# 20190801_MemEx_v1_1.net
KiCad netlist of a schematic drawn in EAGLE
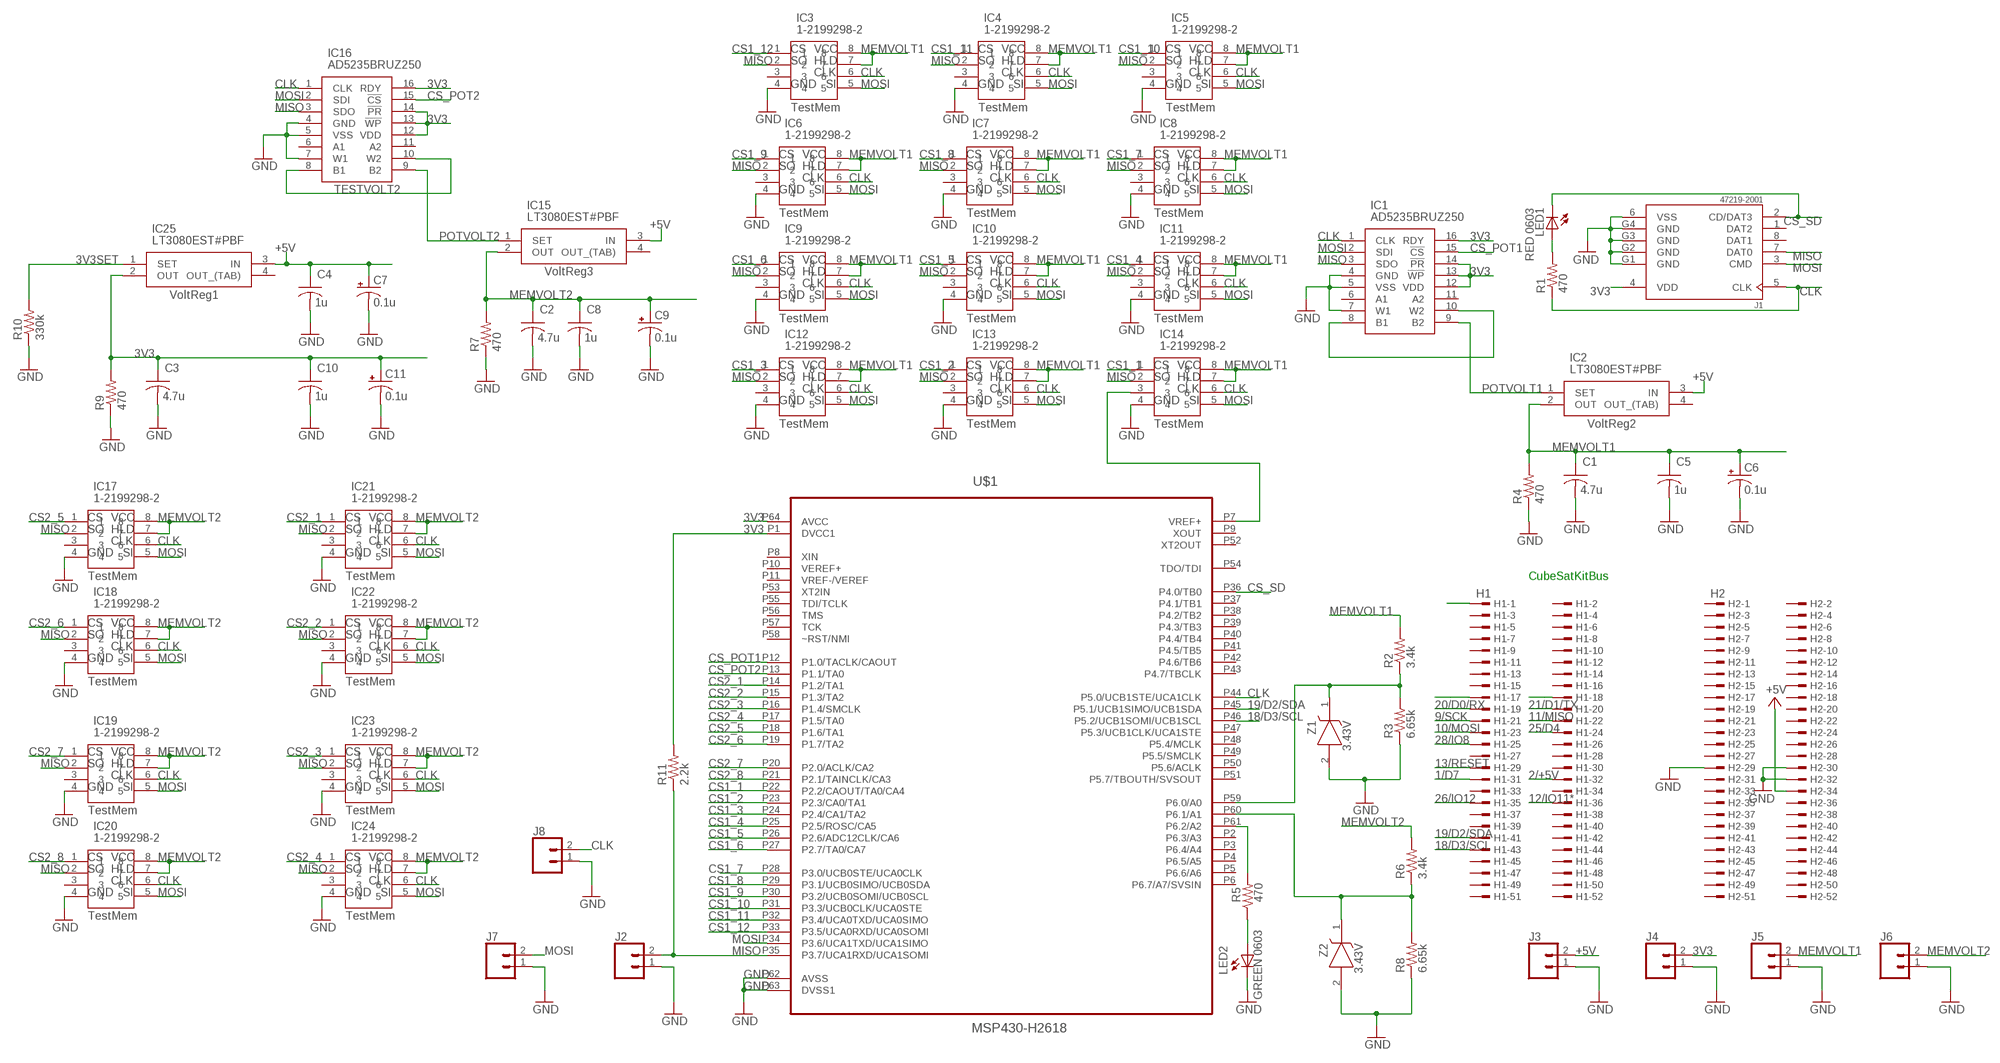
[diagram p0: schematic, sheet 1]

(export (version "E")
  (design (tool "Eeschema 10.0.6"))
  (components
    (comp (ref "C1")
      (value "4.7u")
      (footprint "eagle-import:C0805K")
      (libsource (lib "eagle-import") (part "C-USC0805K"))
    )
    (comp (ref "C2")
      (value "4.7u")
      (footprint "eagle-import:C0805K")
      (libsource (lib "eagle-import") (part "C-USC0805K"))
    )
    (comp (ref "C3")
      (value "4.7u")
      (footprint "eagle-import:C0805K")
      (libsource (lib "eagle-import") (part "C-USC0805K"))
    )
    (comp (ref "C4")
      (value "1u")
      (footprint "eagle-import:C0805K")
      (libsource (lib "eagle-import") (part "C-USC0805K"))
    )
    (comp (ref "C5")
      (value "1u")
      (footprint "eagle-import:C0805K")
      (libsource (lib "eagle-import") (part "C-USC0805K"))
    )
    (comp (ref "C6")
      (value "0.1u")
      (footprint "eagle-import:153CLV-0405")
      (libsource (lib "eagle-import") (part "CPOL-US153CLV-0405"))
    )
    (comp (ref "C7")
      (value "0.1u")
      (footprint "eagle-import:153CLV-0405")
      (libsource (lib "eagle-import") (part "CPOL-US153CLV-0405"))
    )
    (comp (ref "C8")
      (value "1u")
      (footprint "eagle-import:C0805K")
      (libsource (lib "eagle-import") (part "C-USC0805K"))
    )
    (comp (ref "C9")
      (value "0.1u")
      (footprint "eagle-import:153CLV-0405")
      (libsource (lib "eagle-import") (part "CPOL-US153CLV-0405"))
    )
    (comp (ref "C10")
      (value "1u")
      (footprint "eagle-import:C0805K")
      (libsource (lib "eagle-import") (part "C-USC0805K"))
    )
    (comp (ref "C11")
      (value "0.1u")
      (footprint "eagle-import:153CLV-0405")
      (libsource (lib "eagle-import") (part "CPOL-US153CLV-0405"))
    )
    (comp (ref "H1")
      (value "H1")
      (footprint "eagle-import:TSW-126-XX-G-D")
      (fields (field (name "MF") "Samtec Inc.") (field (name "MPN") "TSW-126-07-G-D"))
      (libsource (lib "eagle-import") (part "TSW-126--G-D07"))
    )
    (comp (ref "H2")
      (value "H2")
      (footprint "eagle-import:TSW-126-XX-G-D")
      (fields (field (name "MF") "Samtec Inc.") (field (name "MPN") "TSW-126-07-G-D"))
      (libsource (lib "eagle-import") (part "TSW-126--G-D07"))
    )
    (comp (ref "IC1")
      (value "AD5235BRUZ250")
      (footprint "eagle-import:SOP65P640X120-16N")
      (fields
        (field (name "MOUSER_PART_NUMBER") "584-AD5235BRUZ250")
        (field (name "RS_PART_NUMBER") "0228536")
      )
      (libsource (lib "eagle-import") (part "AD5235BRUZ250"))
    )
    (comp (ref "IC2")
      (value "LT3080EST#PBF")
      (footprint "eagle-import:SOT230P700X180-4N")
      (fields
        (field (name "MOUSER_PART_NUMBER") "584-LT3080EST#PBF")
        (field (name "RS_PART_NUMBER") "9173453")
      )
      (libsource (lib "eagle-import") (part "LT3080EST#PBF"))
    )
    (comp (ref "IC3")
      (value "1-2199298-2")
      (footprint "eagle-import:DIPS762W70P254L1016H510Q8N")
      (fields (field (name "MOUSER_PART_NUMBER") "571-1-2199298-2") (field (name "RS_PART_NUMBER") "1859254"))
      (libsource (lib "eagle-import") (part "1-2199298-2"))
    )
    (comp (ref "IC4")
      (value "1-2199298-2")
      (footprint "eagle-import:DIPS762W70P254L1016H510Q8N")
      (fields (field (name "MOUSER_PART_NUMBER") "571-1-2199298-2") (field (name "RS_PART_NUMBER") "1859254"))
      (libsource (lib "eagle-import") (part "1-2199298-2"))
    )
    (comp (ref "IC5")
      (value "1-2199298-2")
      (footprint "eagle-import:DIPS762W70P254L1016H510Q8N")
      (fields (field (name "MOUSER_PART_NUMBER") "571-1-2199298-2") (field (name "RS_PART_NUMBER") "1859254"))
      (libsource (lib "eagle-import") (part "1-2199298-2"))
    )
    (comp (ref "IC6")
      (value "1-2199298-2")
      (footprint "eagle-import:DIPS762W70P254L1016H510Q8N")
      (fields (field (name "MOUSER_PART_NUMBER") "571-1-2199298-2") (field (name "RS_PART_NUMBER") "1859254"))
      (libsource (lib "eagle-import") (part "1-2199298-2"))
    )
    (comp (ref "IC7")
      (value "1-2199298-2")
      (footprint "eagle-import:DIPS762W70P254L1016H510Q8N")
      (fields (field (name "MOUSER_PART_NUMBER") "571-1-2199298-2") (field (name "RS_PART_NUMBER") "1859254"))
      (libsource (lib "eagle-import") (part "1-2199298-2"))
    )
    (comp (ref "IC8")
      (value "1-2199298-2")
      (footprint "eagle-import:DIPS762W70P254L1016H510Q8N")
      (fields (field (name "MOUSER_PART_NUMBER") "571-1-2199298-2") (field (name "RS_PART_NUMBER") "1859254"))
      (libsource (lib "eagle-import") (part "1-2199298-2"))
    )
    (comp (ref "IC9")
      (value "1-2199298-2")
      (footprint "eagle-import:DIPS762W70P254L1016H510Q8N")
      (fields (field (name "MOUSER_PART_NUMBER") "571-1-2199298-2") (field (name "RS_PART_NUMBER") "1859254"))
      (libsource (lib "eagle-import") (part "1-2199298-2"))
    )
    (comp (ref "IC10")
      (value "1-2199298-2")
      (footprint "eagle-import:DIPS762W70P254L1016H510Q8N")
      (fields (field (name "MOUSER_PART_NUMBER") "571-1-2199298-2") (field (name "RS_PART_NUMBER") "1859254"))
      (libsource (lib "eagle-import") (part "1-2199298-2"))
    )
    (comp (ref "IC11")
      (value "1-2199298-2")
      (footprint "eagle-import:DIPS762W70P254L1016H510Q8N")
      (fields (field (name "MOUSER_PART_NUMBER") "571-1-2199298-2") (field (name "RS_PART_NUMBER") "1859254"))
      (libsource (lib "eagle-import") (part "1-2199298-2"))
    )
    (comp (ref "IC12")
      (value "1-2199298-2")
      (footprint "eagle-import:DIPS762W70P254L1016H510Q8N")
      (fields (field (name "MOUSER_PART_NUMBER") "571-1-2199298-2") (field (name "RS_PART_NUMBER") "1859254"))
      (libsource (lib "eagle-import") (part "1-2199298-2"))
    )
    (comp (ref "IC13")
      (value "1-2199298-2")
      (footprint "eagle-import:DIPS762W70P254L1016H510Q8N")
      (fields (field (name "MOUSER_PART_NUMBER") "571-1-2199298-2") (field (name "RS_PART_NUMBER") "1859254"))
      (libsource (lib "eagle-import") (part "1-2199298-2"))
    )
    (comp (ref "IC14")
      (value "1-2199298-2")
      (footprint "eagle-import:DIPS762W70P254L1016H510Q8N")
      (fields (field (name "MOUSER_PART_NUMBER") "571-1-2199298-2") (field (name "RS_PART_NUMBER") "1859254"))
      (libsource (lib "eagle-import") (part "1-2199298-2"))
    )
    (comp (ref "IC15")
      (value "LT3080EST#PBF")
      (footprint "eagle-import:SOT230P700X180-4N")
      (fields
        (field (name "MOUSER_PART_NUMBER") "584-LT3080EST#PBF")
        (field (name "RS_PART_NUMBER") "9173453")
      )
      (libsource (lib "eagle-import") (part "LT3080EST#PBF"))
    )
    (comp (ref "IC16")
      (value "AD5235BRUZ250")
      (footprint "eagle-import:SOP65P640X120-16N")
      (fields
        (field (name "MOUSER_PART_NUMBER") "584-AD5235BRUZ250")
        (field (name "RS_PART_NUMBER") "0228536")
      )
      (libsource (lib "eagle-import") (part "AD5235BRUZ250"))
    )
    (comp (ref "IC17")
      (value "1-2199298-2")
      (footprint "eagle-import:DIPS762W70P254L1016H510Q8N")
      (fields (field (name "MOUSER_PART_NUMBER") "571-1-2199298-2") (field (name "RS_PART_NUMBER") "1859254"))
      (libsource (lib "eagle-import") (part "1-2199298-2"))
    )
    (comp (ref "IC18")
      (value "1-2199298-2")
      (footprint "eagle-import:DIPS762W70P254L1016H510Q8N")
      (fields (field (name "MOUSER_PART_NUMBER") "571-1-2199298-2") (field (name "RS_PART_NUMBER") "1859254"))
      (libsource (lib "eagle-import") (part "1-2199298-2"))
    )
    (comp (ref "IC19")
      (value "1-2199298-2")
      (footprint "eagle-import:DIPS762W70P254L1016H510Q8N")
      (fields (field (name "MOUSER_PART_NUMBER") "571-1-2199298-2") (field (name "RS_PART_NUMBER") "1859254"))
      (libsource (lib "eagle-import") (part "1-2199298-2"))
    )
    (comp (ref "IC20")
      (value "1-2199298-2")
      (footprint "eagle-import:DIPS762W70P254L1016H510Q8N")
      (fields (field (name "MOUSER_PART_NUMBER") "571-1-2199298-2") (field (name "RS_PART_NUMBER") "1859254"))
      (libsource (lib "eagle-import") (part "1-2199298-2"))
    )
    (comp (ref "IC21")
      (value "1-2199298-2")
      (footprint "eagle-import:DIPS762W70P254L1016H510Q8N")
      (fields (field (name "MOUSER_PART_NUMBER") "571-1-2199298-2") (field (name "RS_PART_NUMBER") "1859254"))
      (libsource (lib "eagle-import") (part "1-2199298-2"))
    )
    (comp (ref "IC22")
      (value "1-2199298-2")
      (footprint "eagle-import:DIPS762W70P254L1016H510Q8N")
      (fields (field (name "MOUSER_PART_NUMBER") "571-1-2199298-2") (field (name "RS_PART_NUMBER") "1859254"))
      (libsource (lib "eagle-import") (part "1-2199298-2"))
    )
    (comp (ref "IC23")
      (value "1-2199298-2")
      (footprint "eagle-import:DIPS762W70P254L1016H510Q8N")
      (fields (field (name "MOUSER_PART_NUMBER") "571-1-2199298-2") (field (name "RS_PART_NUMBER") "1859254"))
      (libsource (lib "eagle-import") (part "1-2199298-2"))
    )
    (comp (ref "IC24")
      (value "1-2199298-2")
      (footprint "eagle-import:DIPS762W70P254L1016H510Q8N")
      (fields (field (name "MOUSER_PART_NUMBER") "571-1-2199298-2") (field (name "RS_PART_NUMBER") "1859254"))
      (libsource (lib "eagle-import") (part "1-2199298-2"))
    )
    (comp (ref "IC25")
      (value "LT3080EST#PBF")
      (footprint "eagle-import:SOT230P700X180-4N")
      (fields
        (field (name "MOUSER_PART_NUMBER") "584-LT3080EST#PBF")
        (field (name "RS_PART_NUMBER") "9173453")
      )
      (libsource (lib "eagle-import") (part "LT3080EST#PBF"))
    )
    (comp (ref "J1")
      (value "47219-2001")
      (footprint "eagle-import:MOLEX_47219-2001")
      (fields (field (name "MF") "Molex"))
      (libsource (lib "eagle-import") (part "47219-2001"))
    )
    (comp (ref "J2")
      (value "CONN_02")
      (footprint "eagle-import:1X02")
      (libsource (lib "eagle-import") (part "CONN_02"))
    )
    (comp (ref "J3")
      (value "CONN_02")
      (footprint "eagle-import:1X02")
      (libsource (lib "eagle-import") (part "CONN_02"))
    )
    (comp (ref "J4")
      (value "CONN_02")
      (footprint "eagle-import:1X02")
      (libsource (lib "eagle-import") (part "CONN_02"))
    )
    (comp (ref "J5")
      (value "CONN_02")
      (footprint "eagle-import:1X02")
      (libsource (lib "eagle-import") (part "CONN_02"))
    )
    (comp (ref "J6")
      (value "CONN_02")
      (footprint "eagle-import:1X02")
      (libsource (lib "eagle-import") (part "CONN_02"))
    )
    (comp (ref "J7")
      (value "CONN_02")
      (footprint "eagle-import:1X02")
      (libsource (lib "eagle-import") (part "CONN_02"))
    )
    (comp (ref "J8")
      (value "CONN_02")
      (footprint "eagle-import:1X02")
      (libsource (lib "eagle-import") (part "CONN_02"))
    )
    (comp (ref "LED1")
      (value "RED 0603")
      (footprint "eagle-import:CHIPLED_0603")
      (libsource (lib "eagle-import") (part "LEDCHIPLED_0603"))
    )
    (comp (ref "LED2")
      (value "GREEN 0603")
      (footprint "eagle-import:CHIPLED_0603")
      (libsource (lib "eagle-import") (part "LEDCHIPLED_0603"))
    )
    (comp (ref "R1")
      (value "470")
      (footprint "eagle-import:R0603")
      (libsource (lib "eagle-import") (part "R-US_R0603"))
    )
    (comp (ref "R2")
      (value "3.4k")
      (footprint "eagle-import:R0603")
      (libsource (lib "eagle-import") (part "R-US_R0603"))
    )
    (comp (ref "R3")
      (value "6.65k")
      (footprint "eagle-import:R0603")
      (libsource (lib "eagle-import") (part "R-US_R0603"))
    )
    (comp (ref "R4")
      (value "470")
      (footprint "eagle-import:R0603")
      (libsource (lib "eagle-import") (part "R-US_R0603"))
    )
    (comp (ref "R5")
      (value "470")
      (footprint "eagle-import:R0603")
      (libsource (lib "eagle-import") (part "R-US_R0603"))
    )
    (comp (ref "R6")
      (value "3.4k")
      (footprint "eagle-import:R0603")
      (libsource (lib "eagle-import") (part "R-US_R0603"))
    )
    (comp (ref "R7")
      (value "470")
      (footprint "eagle-import:R0603")
      (libsource (lib "eagle-import") (part "R-US_R0603"))
    )
    (comp (ref "R8")
      (value "6.65k")
      (footprint "eagle-import:R0603")
      (libsource (lib "eagle-import") (part "R-US_R0603"))
    )
    (comp (ref "R9")
      (value "470")
      (footprint "eagle-import:R0603")
      (libsource (lib "eagle-import") (part "R-US_R0603"))
    )
    (comp (ref "R10")
      (value "330k")
      (footprint "eagle-import:R0603")
      (libsource (lib "eagle-import") (part "R-US_R0603"))
    )
    (comp (ref "R11")
      (value "2.2k")
      (footprint "eagle-import:R0603")
      (libsource (lib "eagle-import") (part "R-US_R0603"))
    )
    (comp (ref "U$1")
      (value "MSP430-H2618")
      (footprint "eagle-import:MSP430-H2618")
      (libsource (lib "eagle-import") (part "MSP430-H2618"))
    )
    (comp (ref "Z1")
      (value "3.43V")
      (footprint "eagle-import:SODFL2513X70N")
      (fields
        (field (name "MANUFACTURER_PART_NUMBER") "PLZ3V3B-G3/H")
        (field (name "MOUSER_PART_NUMBER") "78-PLZ3V3B-G3/H")
      )
      (libsource (lib "eagle-import") (part "PLZ3V3B-G3_H"))
    )
    (comp (ref "Z2")
      (value "3.43V")
      (footprint "eagle-import:SODFL2513X70N")
      (fields
        (field (name "MANUFACTURER_PART_NUMBER") "PLZ3V3B-G3/H")
        (field (name "MOUSER_PART_NUMBER") "78-PLZ3V3B-G3/H")
      )
      (libsource (lib "eagle-import") (part "PLZ3V3B-G3_H"))
    )
  )
  (nets
    (net (code "1") (name "+5V") (class "Default")
      (node (ref "C4") (pin "1") (pinfunction "1_1") (pintype "passive"))
      (node (ref "C7") (pin "+") (pinfunction "+_+") (pintype "passive"))
      (node (ref "H2") (pin "34") (pinfunction "1_34") (pintype "passive"))
      (node (ref "IC15") (pin "3") (pinfunction "IN_3") (pintype "power_in"))
      (node (ref "IC2") (pin "3") (pinfunction "IN_3") (pintype "power_in"))
      (node (ref "IC25") (pin "3") (pinfunction "IN_3") (pintype "power_in"))
      (node (ref "J3") (pin "2") (pinfunction "2_2") (pintype "passive"))
    )
    (net (code "2") (name "/1{slash}D7") (class "Default")
      (node (ref "H1") (pin "31") (pinfunction "1_31") (pintype "passive"))
    )
    (net (code "3") (name "/2{slash}+5V") (class "Default")
      (node (ref "H1") (pin "32") (pinfunction "1_32") (pintype "passive"))
    )
    (net (code "4") (name "/3V3") (class "Default")
      (node (ref "C10") (pin "1") (pinfunction "1_1") (pintype "passive"))
      (node (ref "C11") (pin "+") (pinfunction "+_+") (pintype "passive"))
      (node (ref "C3") (pin "1") (pinfunction "1_1") (pintype "passive"))
      (node (ref "IC1") (pin "12") (pinfunction "VDD_12") (pintype "power_in"))
      (node (ref "IC1") (pin "13") (pinfunction "~{WP}_13") (pintype "bidirectional"))
      (node (ref "IC1") (pin "14") (pinfunction "~{PR}_14") (pintype "bidirectional"))
      (node (ref "IC1") (pin "16") (pinfunction "RDY_16") (pintype "bidirectional"))
      (node (ref "IC16") (pin "12") (pinfunction "VDD_12") (pintype "power_in"))
      (node (ref "IC16") (pin "13") (pinfunction "~{WP}_13") (pintype "bidirectional"))
      (node (ref "IC16") (pin "14") (pinfunction "~{PR}_14") (pintype "bidirectional"))
      (node (ref "IC16") (pin "16") (pinfunction "RDY_16") (pintype "bidirectional"))
      (node (ref "IC25") (pin "2") (pinfunction "OUT_2") (pintype "output"))
      (node (ref "J1") (pin "4") (pinfunction "VDD_4") (pintype "power_in"))
      (node (ref "J4") (pin "2") (pinfunction "2_2") (pintype "passive"))
      (node (ref "R11") (pin "2") (pinfunction "2_2") (pintype "passive"))
      (node (ref "R9") (pin "2") (pinfunction "2_2") (pintype "passive"))
      (node (ref "U$1") (pin "P1") (pinfunction "DVCC1_P1") (pintype "power_in"))
      (node (ref "U$1") (pin "P64") (pinfunction "AVCC_P64") (pintype "power_in"))
    )
    (net (code "5") (name "/3V3SET") (class "Default")
      (node (ref "IC25") (pin "1") (pinfunction "SET_1") (pintype "input"))
      (node (ref "R10") (pin "2") (pinfunction "2_2") (pintype "passive"))
    )
    (net (code "6") (name "/9{slash}SCK") (class "Default")
      (node (ref "H1") (pin "21") (pinfunction "1_21") (pintype "passive"))
    )
    (net (code "7") (name "/10{slash}MOSI") (class "Default")
      (node (ref "H1") (pin "23") (pinfunction "1_23") (pintype "passive"))
    )
    (net (code "8") (name "/11{slash}MISO") (class "Default")
      (node (ref "H1") (pin "22") (pinfunction "1_22") (pintype "passive"))
    )
    (net (code "9") (name "/12{slash}IO11*") (class "Default")
      (node (ref "H1") (pin "36") (pinfunction "1_36") (pintype "passive"))
    )
    (net (code "10") (name "/13{slash}RESET") (class "Default")
      (node (ref "H1") (pin "29") (pinfunction "1_29") (pintype "passive"))
    )
    (net (code "11") (name "/18{slash}D3{slash}SCL") (class "Default")
      (node (ref "H1") (pin "43") (pinfunction "1_43") (pintype "passive"))
      (node (ref "U$1") (pin "P46") (pinfunction "P5.2/UCB1SOMI/UCB1SCL_P46") (pintype "bidirectional"))
    )
    (net (code "12") (name "/19{slash}D2{slash}SDA") (class "Default")
      (node (ref "H1") (pin "41") (pinfunction "1_41") (pintype "passive"))
      (node (ref "U$1") (pin "P45") (pinfunction "P5.1/UCB1SIMO/UCB1SDA_P45") (pintype "bidirectional"))
    )
    (net (code "13") (name "/20{slash}D0{slash}RX") (class "Default")
      (node (ref "H1") (pin "19") (pinfunction "1_19") (pintype "passive"))
    )
    (net (code "14") (name "/21{slash}D1{slash}TX") (class "Default")
      (node (ref "H1") (pin "20") (pinfunction "1_20") (pintype "passive"))
    )
    (net (code "15") (name "/25{slash}D4") (class "Default")
      (node (ref "H1") (pin "24") (pinfunction "1_24") (pintype "passive"))
    )
    (net (code "16") (name "/26{slash}IO12") (class "Default")
      (node (ref "H1") (pin "35") (pinfunction "1_35") (pintype "passive"))
    )
    (net (code "17") (name "/28{slash}IO8") (class "Default")
      (node (ref "H1") (pin "25") (pinfunction "1_25") (pintype "passive"))
    )
    (net (code "18") (name "/CLK") (class "Default")
      (node (ref "IC1") (pin "1") (pinfunction "CLK_1") (pintype "input"))
      (node (ref "IC10") (pin "6") (pinfunction "6_6") (pintype "bidirectional"))
      (node (ref "IC11") (pin "6") (pinfunction "6_6") (pintype "bidirectional"))
      (node (ref "IC12") (pin "6") (pinfunction "6_6") (pintype "bidirectional"))
      (node (ref "IC13") (pin "6") (pinfunction "6_6") (pintype "bidirectional"))
      (node (ref "IC14") (pin "6") (pinfunction "6_6") (pintype "bidirectional"))
      (node (ref "IC16") (pin "1") (pinfunction "CLK_1") (pintype "input"))
      (node (ref "IC17") (pin "6") (pinfunction "6_6") (pintype "bidirectional"))
      (node (ref "IC18") (pin "6") (pinfunction "6_6") (pintype "bidirectional"))
      (node (ref "IC19") (pin "6") (pinfunction "6_6") (pintype "bidirectional"))
      (node (ref "IC20") (pin "6") (pinfunction "6_6") (pintype "bidirectional"))
      (node (ref "IC21") (pin "6") (pinfunction "6_6") (pintype "bidirectional"))
      (node (ref "IC22") (pin "6") (pinfunction "6_6") (pintype "bidirectional"))
      (node (ref "IC23") (pin "6") (pinfunction "6_6") (pintype "bidirectional"))
      (node (ref "IC24") (pin "6") (pinfunction "6_6") (pintype "bidirectional"))
      (node (ref "IC3") (pin "6") (pinfunction "6_6") (pintype "bidirectional"))
      (node (ref "IC4") (pin "6") (pinfunction "6_6") (pintype "bidirectional"))
      (node (ref "IC5") (pin "6") (pinfunction "6_6") (pintype "bidirectional"))
      (node (ref "IC6") (pin "6") (pinfunction "6_6") (pintype "bidirectional"))
      (node (ref "IC7") (pin "6") (pinfunction "6_6") (pintype "bidirectional"))
      (node (ref "IC8") (pin "6") (pinfunction "6_6") (pintype "bidirectional"))
      (node (ref "IC9") (pin "6") (pinfunction "6_6") (pintype "bidirectional"))
      (node (ref "J1") (pin "5") (pinfunction "CLK_5") (pintype "input"))
      (node (ref "J8") (pin "2") (pinfunction "2_2") (pintype "passive"))
      (node (ref "R1") (pin "1") (pinfunction "1_1") (pintype "passive"))
      (node (ref "U$1") (pin "P44") (pinfunction "P5.0/UCB1STE/UCA1CLK_P44") (pintype "bidirectional"))
    )
    (net (code "19") (name "/CS1_1") (class "Default")
      (node (ref "IC14") (pin "1") (pinfunction "1_1") (pintype "bidirectional"))
      (node (ref "U$1") (pin "P22") (pinfunction "P2.2/CAOUT/TA0/CA4_P22") (pintype "bidirectional"))
    )
    (net (code "20") (name "/CS1_2") (class "Default")
      (node (ref "IC13") (pin "1") (pinfunction "1_1") (pintype "bidirectional"))
      (node (ref "U$1") (pin "P23") (pinfunction "P2.3/CA0/TA1_P23") (pintype "bidirectional"))
    )
    (net (code "21") (name "/CS1_3") (class "Default")
      (node (ref "IC12") (pin "1") (pinfunction "1_1") (pintype "bidirectional"))
      (node (ref "U$1") (pin "P24") (pinfunction "P2.4/CA1/TA2_P24") (pintype "bidirectional"))
    )
    (net (code "22") (name "/CS1_4") (class "Default")
      (node (ref "IC11") (pin "1") (pinfunction "1_1") (pintype "bidirectional"))
      (node (ref "U$1") (pin "P25") (pinfunction "P2.5/ROSC/CA5_P25") (pintype "bidirectional"))
    )
    (net (code "23") (name "/CS1_5") (class "Default")
      (node (ref "IC10") (pin "1") (pinfunction "1_1") (pintype "bidirectional"))
      (node (ref "U$1") (pin "P26") (pinfunction "P2.6/ADC12CLK/CA6_P26") (pintype "bidirectional"))
    )
    (net (code "24") (name "/CS1_6") (class "Default")
      (node (ref "IC9") (pin "1") (pinfunction "1_1") (pintype "bidirectional"))
      (node (ref "U$1") (pin "P27") (pinfunction "P2.7/TA0/CA7_P27") (pintype "bidirectional"))
    )
    (net (code "25") (name "/CS1_7") (class "Default")
      (node (ref "IC8") (pin "1") (pinfunction "1_1") (pintype "bidirectional"))
      (node (ref "U$1") (pin "P28") (pinfunction "P3.0/UCB0STE/UCA0CLK_P28") (pintype "bidirectional"))
    )
    (net (code "26") (name "/CS1_8") (class "Default")
      (node (ref "IC7") (pin "1") (pinfunction "1_1") (pintype "bidirectional"))
      (node (ref "U$1") (pin "P29") (pinfunction "P3.1/UCB0SIMO/UCB0SDA_P29") (pintype "bidirectional"))
    )
    (net (code "27") (name "/CS1_9") (class "Default")
      (node (ref "IC6") (pin "1") (pinfunction "1_1") (pintype "bidirectional"))
      (node (ref "U$1") (pin "P30") (pinfunction "P3.2/UCB0SOMI/UCB0SCL_P30") (pintype "bidirectional"))
    )
    (net (code "28") (name "/CS1_10") (class "Default")
      (node (ref "IC5") (pin "1") (pinfunction "1_1") (pintype "bidirectional"))
      (node (ref "U$1") (pin "P31") (pinfunction "P3.3/UCB0CLK/UCA0STE_P31") (pintype "bidirectional"))
    )
    (net (code "29") (name "/CS1_11") (class "Default")
      (node (ref "IC4") (pin "1") (pinfunction "1_1") (pintype "bidirectional"))
      (node (ref "U$1") (pin "P32") (pinfunction "P3.4/UCA0TXD/UCA0SIMO_P32") (pintype "bidirectional"))
    )
    (net (code "30") (name "/CS1_12") (class "Default")
      (node (ref "IC3") (pin "1") (pinfunction "1_1") (pintype "bidirectional"))
      (node (ref "U$1") (pin "P33") (pinfunction "P3.5/UCA0RXD/UCA0SOMI_P33") (pintype "bidirectional"))
    )
    (net (code "31") (name "/CS2_1") (class "Default")
      (node (ref "IC21") (pin "1") (pinfunction "1_1") (pintype "bidirectional"))
      (node (ref "U$1") (pin "P14") (pinfunction "P1.2/TA1_P14") (pintype "bidirectional"))
    )
    (net (code "32") (name "/CS2_2") (class "Default")
      (node (ref "IC22") (pin "1") (pinfunction "1_1") (pintype "bidirectional"))
      (node (ref "U$1") (pin "P15") (pinfunction "P1.3/TA2_P15") (pintype "bidirectional"))
    )
    (net (code "33") (name "/CS2_3") (class "Default")
      (node (ref "IC23") (pin "1") (pinfunction "1_1") (pintype "bidirectional"))
      (node (ref "U$1") (pin "P16") (pinfunction "P1.4/SMCLK_P16") (pintype "bidirectional"))
    )
    (net (code "34") (name "/CS2_4") (class "Default")
      (node (ref "IC24") (pin "1") (pinfunction "1_1") (pintype "bidirectional"))
      (node (ref "U$1") (pin "P17") (pinfunction "P1.5/TA0_P17") (pintype "bidirectional"))
    )
    (net (code "35") (name "/CS2_5") (class "Default")
      (node (ref "IC17") (pin "1") (pinfunction "1_1") (pintype "bidirectional"))
      (node (ref "U$1") (pin "P18") (pinfunction "P1.6/TA1_P18") (pintype "bidirectional"))
    )
    (net (code "36") (name "/CS2_6") (class "Default")
      (node (ref "IC18") (pin "1") (pinfunction "1_1") (pintype "bidirectional"))
      (node (ref "U$1") (pin "P19") (pinfunction "P1.7/TA2_P19") (pintype "bidirectional"))
    )
    (net (code "37") (name "/CS2_7") (class "Default")
      (node (ref "IC19") (pin "1") (pinfunction "1_1") (pintype "bidirectional"))
      (node (ref "U$1") (pin "P20") (pinfunction "P2.0/ACLK/CA2_P20") (pintype "bidirectional"))
    )
    (net (code "38") (name "/CS2_8") (class "Default")
      (node (ref "IC20") (pin "1") (pinfunction "1_1") (pintype "bidirectional"))
      (node (ref "U$1") (pin "P21") (pinfunction "P2.1/TAINCLK/CA3_P21") (pintype "bidirectional"))
    )
    (net (code "39") (name "/CS_POT1") (class "Default")
      (node (ref "IC1") (pin "15") (pinfunction "~{CS}_15") (pintype "input"))
      (node (ref "U$1") (pin "P12") (pinfunction "P1.0/TACLK/CAOUT_P12") (pintype "bidirectional"))
    )
    (net (code "40") (name "/CS_POT2") (class "Default")
      (node (ref "IC16") (pin "15") (pinfunction "~{CS}_15") (pintype "input"))
      (node (ref "U$1") (pin "P13") (pinfunction "P1.1/TA0_P13") (pintype "bidirectional"))
    )
    (net (code "41") (name "/CS_SD") (class "Default")
      (node (ref "J1") (pin "2") (pinfunction "CD/DAT3_2") (pintype "bidirectional"))
      (node (ref "LED1") (pin "C") (pinfunction "C_C") (pintype "passive"))
      (node (ref "U$1") (pin "P36") (pinfunction "P4.0/TB0_P36") (pintype "bidirectional"))
    )
    (net (code "42") (name "/MEMVOLT1") (class "Default")
      (node (ref "C1") (pin "1") (pinfunction "1_1") (pintype "passive"))
      (node (ref "C5") (pin "1") (pinfunction "1_1") (pintype "passive"))
      (node (ref "C6") (pin "+") (pinfunction "+_+") (pintype "passive"))
      (node (ref "IC10") (pin "7") (pinfunction "7_7") (pintype "bidirectional"))
      (node (ref "IC10") (pin "8") (pinfunction "8_8") (pintype "bidirectional"))
      (node (ref "IC11") (pin "7") (pinfunction "7_7") (pintype "bidirectional"))
      (node (ref "IC11") (pin "8") (pinfunction "8_8") (pintype "bidirectional"))
      (node (ref "IC12") (pin "7") (pinfunction "7_7") (pintype "bidirectional"))
      (node (ref "IC12") (pin "8") (pinfunction "8_8") (pintype "bidirectional"))
      (node (ref "IC13") (pin "7") (pinfunction "7_7") (pintype "bidirectional"))
      (node (ref "IC13") (pin "8") (pinfunction "8_8") (pintype "bidirectional"))
      (node (ref "IC14") (pin "7") (pinfunction "7_7") (pintype "bidirectional"))
      (node (ref "IC14") (pin "8") (pinfunction "8_8") (pintype "bidirectional"))
      (node (ref "IC2") (pin "2") (pinfunction "OUT_2") (pintype "output"))
      (node (ref "IC3") (pin "7") (pinfunction "7_7") (pintype "bidirectional"))
      (node (ref "IC3") (pin "8") (pinfunction "8_8") (pintype "bidirectional"))
      (node (ref "IC4") (pin "7") (pinfunction "7_7") (pintype "bidirectional"))
      (node (ref "IC4") (pin "8") (pinfunction "8_8") (pintype "bidirectional"))
      (node (ref "IC5") (pin "7") (pinfunction "7_7") (pintype "bidirectional"))
      (node (ref "IC5") (pin "8") (pinfunction "8_8") (pintype "bidirectional"))
      (node (ref "IC6") (pin "7") (pinfunction "7_7") (pintype "bidirectional"))
      (node (ref "IC6") (pin "8") (pinfunction "8_8") (pintype "bidirectional"))
      (node (ref "IC7") (pin "7") (pinfunction "7_7") (pintype "bidirectional"))
      (node (ref "IC7") (pin "8") (pinfunction "8_8") (pintype "bidirectional"))
      (node (ref "IC8") (pin "7") (pinfunction "7_7") (pintype "bidirectional"))
      (node (ref "IC8") (pin "8") (pinfunction "8_8") (pintype "bidirectional"))
      (node (ref "IC9") (pin "7") (pinfunction "7_7") (pintype "bidirectional"))
      (node (ref "IC9") (pin "8") (pinfunction "8_8") (pintype "bidirectional"))
      (node (ref "J5") (pin "2") (pinfunction "2_2") (pintype "passive"))
      (node (ref "R2") (pin "2") (pinfunction "2_2") (pintype "passive"))
      (node (ref "R4") (pin "2") (pinfunction "2_2") (pintype "passive"))
    )
    (net (code "43") (name "/MEMVOLT2") (class "Default")
      (node (ref "C2") (pin "1") (pinfunction "1_1") (pintype "passive"))
      (node (ref "C8") (pin "1") (pinfunction "1_1") (pintype "passive"))
      (node (ref "C9") (pin "+") (pinfunction "+_+") (pintype "passive"))
      (node (ref "IC15") (pin "2") (pinfunction "OUT_2") (pintype "output"))
      (node (ref "IC17") (pin "7") (pinfunction "7_7") (pintype "bidirectional"))
      (node (ref "IC17") (pin "8") (pinfunction "8_8") (pintype "bidirectional"))
      (node (ref "IC18") (pin "7") (pinfunction "7_7") (pintype "bidirectional"))
      (node (ref "IC18") (pin "8") (pinfunction "8_8") (pintype "bidirectional"))
      (node (ref "IC19") (pin "7") (pinfunction "7_7") (pintype "bidirectional"))
      (node (ref "IC19") (pin "8") (pinfunction "8_8") (pintype "bidirectional"))
      (node (ref "IC20") (pin "7") (pinfunction "7_7") (pintype "bidirectional"))
      (node (ref "IC20") (pin "8") (pinfunction "8_8") (pintype "bidirectional"))
      (node (ref "IC21") (pin "7") (pinfunction "7_7") (pintype "bidirectional"))
      (node (ref "IC21") (pin "8") (pinfunction "8_8") (pintype "bidirectional"))
      (node (ref "IC22") (pin "7") (pinfunction "7_7") (pintype "bidirectional"))
      (node (ref "IC22") (pin "8") (pinfunction "8_8") (pintype "bidirectional"))
      (node (ref "IC23") (pin "7") (pinfunction "7_7") (pintype "bidirectional"))
      (node (ref "IC23") (pin "8") (pinfunction "8_8") (pintype "bidirectional"))
      (node (ref "IC24") (pin "7") (pinfunction "7_7") (pintype "bidirectional"))
      (node (ref "IC24") (pin "8") (pinfunction "8_8") (pintype "bidirectional"))
      (node (ref "J6") (pin "2") (pinfunction "2_2") (pintype "passive"))
      (node (ref "R6") (pin "2") (pinfunction "2_2") (pintype "passive"))
      (node (ref "R7") (pin "2") (pinfunction "2_2") (pintype "passive"))
    )
    (net (code "44") (name "/MISO") (class "Default")
      (node (ref "IC1") (pin "3") (pinfunction "SDO_3") (pintype "bidirectional"))
      (node (ref "IC10") (pin "2") (pinfunction "2_2") (pintype "bidirectional"))
      (node (ref "IC11") (pin "2") (pinfunction "2_2") (pintype "bidirectional"))
      (node (ref "IC12") (pin "2") (pinfunction "2_2") (pintype "bidirectional"))
      (node (ref "IC13") (pin "2") (pinfunction "2_2") (pintype "bidirectional"))
      (node (ref "IC14") (pin "2") (pinfunction "2_2") (pintype "bidirectional"))
      (node (ref "IC16") (pin "3") (pinfunction "SDO_3") (pintype "bidirectional"))
      (node (ref "IC17") (pin "2") (pinfunction "2_2") (pintype "bidirectional"))
      (node (ref "IC18") (pin "2") (pinfunction "2_2") (pintype "bidirectional"))
      (node (ref "IC19") (pin "2") (pinfunction "2_2") (pintype "bidirectional"))
      (node (ref "IC20") (pin "2") (pinfunction "2_2") (pintype "bidirectional"))
      (node (ref "IC21") (pin "2") (pinfunction "2_2") (pintype "bidirectional"))
      (node (ref "IC22") (pin "2") (pinfunction "2_2") (pintype "bidirectional"))
      (node (ref "IC23") (pin "2") (pinfunction "2_2") (pintype "bidirectional"))
      (node (ref "IC24") (pin "2") (pinfunction "2_2") (pintype "bidirectional"))
      (node (ref "IC3") (pin "2") (pinfunction "2_2") (pintype "bidirectional"))
      (node (ref "IC4") (pin "2") (pinfunction "2_2") (pintype "bidirectional"))
      (node (ref "IC5") (pin "2") (pinfunction "2_2") (pintype "bidirectional"))
      (node (ref "IC6") (pin "2") (pinfunction "2_2") (pintype "bidirectional"))
      (node (ref "IC7") (pin "2") (pinfunction "2_2") (pintype "bidirectional"))
      (node (ref "IC8") (pin "2") (pinfunction "2_2") (pintype "bidirectional"))
      (node (ref "IC9") (pin "2") (pinfunction "2_2") (pintype "bidirectional"))
      (node (ref "J1") (pin "7") (pinfunction "DAT0_7") (pintype "bidirectional"))
      (node (ref "J2") (pin "2") (pinfunction "2_2") (pintype "passive"))
      (node (ref "R11") (pin "1") (pinfunction "1_1") (pintype "passive"))
      (node (ref "U$1") (pin "P35") (pinfunction "P3.7/UCA1RXD/UCA1SOMI_P35") (pintype "bidirectional"))
    )
    (net (code "45") (name "/MOSI") (class "Default")
      (node (ref "IC1") (pin "2") (pinfunction "SDI_2") (pintype "bidirectional"))
      (node (ref "IC10") (pin "5") (pinfunction "5_5") (pintype "bidirectional"))
      (node (ref "IC11") (pin "5") (pinfunction "5_5") (pintype "bidirectional"))
      (node (ref "IC12") (pin "5") (pinfunction "5_5") (pintype "bidirectional"))
      (node (ref "IC13") (pin "5") (pinfunction "5_5") (pintype "bidirectional"))
      (node (ref "IC14") (pin "5") (pinfunction "5_5") (pintype "bidirectional"))
      (node (ref "IC16") (pin "2") (pinfunction "SDI_2") (pintype "bidirectional"))
      (node (ref "IC17") (pin "5") (pinfunction "5_5") (pintype "bidirectional"))
      (node (ref "IC18") (pin "5") (pinfunction "5_5") (pintype "bidirectional"))
      (node (ref "IC19") (pin "5") (pinfunction "5_5") (pintype "bidirectional"))
      (node (ref "IC20") (pin "5") (pinfunction "5_5") (pintype "bidirectional"))
      (node (ref "IC21") (pin "5") (pinfunction "5_5") (pintype "bidirectional"))
      (node (ref "IC22") (pin "5") (pinfunction "5_5") (pintype "bidirectional"))
      (node (ref "IC23") (pin "5") (pinfunction "5_5") (pintype "bidirectional"))
      (node (ref "IC24") (pin "5") (pinfunction "5_5") (pintype "bidirectional"))
      (node (ref "IC3") (pin "5") (pinfunction "5_5") (pintype "bidirectional"))
      (node (ref "IC4") (pin "5") (pinfunction "5_5") (pintype "bidirectional"))
      (node (ref "IC5") (pin "5") (pinfunction "5_5") (pintype "bidirectional"))
      (node (ref "IC6") (pin "5") (pinfunction "5_5") (pintype "bidirectional"))
      (node (ref "IC7") (pin "5") (pinfunction "5_5") (pintype "bidirectional"))
      (node (ref "IC8") (pin "5") (pinfunction "5_5") (pintype "bidirectional"))
      (node (ref "IC9") (pin "5") (pinfunction "5_5") (pintype "bidirectional"))
      (node (ref "J1") (pin "3") (pinfunction "CMD_3") (pintype "bidirectional"))
      (node (ref "J7") (pin "2") (pinfunction "2_2") (pintype "passive"))
      (node (ref "U$1") (pin "P34") (pinfunction "P3.6/UCA1TXD/UCA1SIMO_P34") (pintype "bidirectional"))
    )
    (net (code "46") (name "/POTVOLT1") (class "Default")
      (node (ref "IC1") (pin "9") (pinfunction "B2_9") (pintype "bidirectional"))
      (node (ref "IC2") (pin "1") (pinfunction "SET_1") (pintype "input"))
    )
    (net (code "47") (name "/POTVOLT2") (class "Default")
      (node (ref "IC15") (pin "1") (pinfunction "SET_1") (pintype "input"))
      (node (ref "IC16") (pin "9") (pinfunction "B2_9") (pintype "bidirectional"))
    )
    (net (code "48") (name "/TESTVOLT2") (class "Default")
      (node (ref "IC16") (pin "10") (pinfunction "W2_10") (pintype "bidirectional"))
      (node (ref "IC16") (pin "8") (pinfunction "B1_8") (pintype "bidirectional"))
    )
    (net (code "49") (name "GND") (class "Default")
      (node (ref "C1") (pin "2") (pinfunction "2_2") (pintype "passive"))
      (node (ref "C10") (pin "2") (pinfunction "2_2") (pintype "passive"))
      (node (ref "C11") (pin "-") (pinfunction "-_-") (pintype "passive"))
      (node (ref "C2") (pin "2") (pinfunction "2_2") (pintype "passive"))
      (node (ref "C3") (pin "2") (pinfunction "2_2") (pintype "passive"))
      (node (ref "C4") (pin "2") (pinfunction "2_2") (pintype "passive"))
      (node (ref "C5") (pin "2") (pinfunction "2_2") (pintype "passive"))
      (node (ref "C6") (pin "-") (pinfunction "-_-") (pintype "passive"))
      (node (ref "C7") (pin "-") (pinfunction "-_-") (pintype "passive"))
      (node (ref "C8") (pin "2") (pinfunction "2_2") (pintype "passive"))
      (node (ref "C9") (pin "-") (pinfunction "-_-") (pintype "passive"))
      (node (ref "H2") (pin "29") (pinfunction "1_29") (pintype "passive"))
      (node (ref "H2") (pin "30") (pinfunction "1_30") (pintype "passive"))
      (node (ref "H2") (pin "32") (pinfunction "1_32") (pintype "passive"))
      (node (ref "IC1") (pin "4") (pinfunction "GND_4") (pintype "power_in"))
      (node (ref "IC1") (pin "5") (pinfunction "VSS_5") (pintype "power_in"))
      (node (ref "IC1") (pin "7") (pinfunction "W1_7") (pintype "bidirectional"))
      (node (ref "IC10") (pin "4") (pinfunction "4_4") (pintype "bidirectional"))
      (node (ref "IC11") (pin "4") (pinfunction "4_4") (pintype "bidirectional"))
      (node (ref "IC12") (pin "4") (pinfunction "4_4") (pintype "bidirectional"))
      (node (ref "IC13") (pin "4") (pinfunction "4_4") (pintype "bidirectional"))
      (node (ref "IC14") (pin "4") (pinfunction "4_4") (pintype "bidirectional"))
      (node (ref "IC16") (pin "4") (pinfunction "GND_4") (pintype "power_in"))
      (node (ref "IC16") (pin "5") (pinfunction "VSS_5") (pintype "power_in"))
      (node (ref "IC16") (pin "7") (pinfunction "W1_7") (pintype "bidirectional"))
      (node (ref "IC17") (pin "4") (pinfunction "4_4") (pintype "bidirectional"))
      (node (ref "IC18") (pin "4") (pinfunction "4_4") (pintype "bidirectional"))
      (node (ref "IC19") (pin "4") (pinfunction "4_4") (pintype "bidirectional"))
      (node (ref "IC20") (pin "4") (pinfunction "4_4") (pintype "bidirectional"))
      (node (ref "IC21") (pin "4") (pinfunction "4_4") (pintype "bidirectional"))
      (node (ref "IC22") (pin "4") (pinfunction "4_4") (pintype "bidirectional"))
      (node (ref "IC23") (pin "4") (pinfunction "4_4") (pintype "bidirectional"))
      (node (ref "IC24") (pin "4") (pinfunction "4_4") (pintype "bidirectional"))
      (node (ref "IC3") (pin "4") (pinfunction "4_4") (pintype "bidirectional"))
      (node (ref "IC4") (pin "4") (pinfunction "4_4") (pintype "bidirectional"))
      (node (ref "IC5") (pin "4") (pinfunction "4_4") (pintype "bidirectional"))
      (node (ref "IC6") (pin "4") (pinfunction "4_4") (pintype "bidirectional"))
      (node (ref "IC7") (pin "4") (pinfunction "4_4") (pintype "bidirectional"))
      (node (ref "IC8") (pin "4") (pinfunction "4_4") (pintype "bidirectional"))
      (node (ref "IC9") (pin "4") (pinfunction "4_4") (pintype "bidirectional"))
      (node (ref "J1") (pin "6") (pinfunction "VSS_6") (pintype "power_in"))
      (node (ref "J1") (pin "G1") (pinfunction "GND_G1") (pintype "power_in"))
      (node (ref "J1") (pin "G2") (pinfunction "GND_G2") (pintype "power_in"))
      (node (ref "J1") (pin "G3") (pinfunction "GND_G3") (pintype "power_in"))
      (node (ref "J1") (pin "G4") (pinfunction "GND_G4") (pintype "power_in"))
      (node (ref "J2") (pin "1") (pinfunction "1_1") (pintype "passive"))
      (node (ref "J3") (pin "1") (pinfunction "1_1") (pintype "passive"))
      (node (ref "J4") (pin "1") (pinfunction "1_1") (pintype "passive"))
      (node (ref "J5") (pin "1") (pinfunction "1_1") (pintype "passive"))
      (node (ref "J6") (pin "1") (pinfunction "1_1") (pintype "passive"))
      (node (ref "J7") (pin "1") (pinfunction "1_1") (pintype "passive"))
      (node (ref "J8") (pin "1") (pinfunction "1_1") (pintype "passive"))
      (node (ref "LED2") (pin "C") (pinfunction "C_C") (pintype "passive"))
      (node (ref "R10") (pin "1") (pinfunction "1_1") (pintype "passive"))
      (node (ref "R3") (pin "1") (pinfunction "1_1") (pintype "passive"))
      (node (ref "R4") (pin "1") (pinfunction "1_1") (pintype "passive"))
      (node (ref "R7") (pin "1") (pinfunction "1_1") (pintype "passive"))
      (node (ref "R8") (pin "1") (pinfunction "1_1") (pintype "passive"))
      (node (ref "R9") (pin "1") (pinfunction "1_1") (pintype "passive"))
      (node (ref "U$1") (pin "P62") (pinfunction "AVSS_P62") (pintype "power_in"))
      (node (ref "U$1") (pin "P63") (pinfunction "DVSS1_P63") (pintype "power_in"))
      (node (ref "Z1") (pin "2") (pinfunction "A_2") (pintype "bidirectional"))
      (node (ref "Z2") (pin "2") (pinfunction "A_2") (pintype "bidirectional"))
    )
    (net (code "50") (name "Net-(IC1-B1)") (class "Default")
      (node (ref "IC1") (pin "10") (pinfunction "W2_10") (pintype "bidirectional"))
      (node (ref "IC1") (pin "8") (pinfunction "B1_8") (pintype "bidirectional"))
    )
    (net (code "51") (name "Net-(LED1-PadA)") (class "Default")
      (node (ref "LED1") (pin "A") (pinfunction "A_A") (pintype "passive"))
      (node (ref "R1") (pin "2") (pinfunction "2_2") (pintype "passive"))
    )
    (net (code "52") (name "Net-(LED2-PadA)") (class "Default")
      (node (ref "LED2") (pin "A") (pinfunction "A_A") (pintype "passive"))
      (node (ref "R5") (pin "1") (pinfunction "1_1") (pintype "passive"))
    )
    (net (code "53") (name "Net-(U$1-P6.0{slash}A0)") (class "Default")
      (node (ref "R2") (pin "1") (pinfunction "1_1") (pintype "passive"))
      (node (ref "R3") (pin "2") (pinfunction "2_2") (pintype "passive"))
      (node (ref "U$1") (pin "P59") (pinfunction "P6.0/A0_P59") (pintype "bidirectional"))
      (node (ref "Z1") (pin "1") (pinfunction "K_1") (pintype "bidirectional"))
    )
    (net (code "54") (name "Net-(U$1-P6.1{slash}A1)") (class "Default")
      (node (ref "R6") (pin "1") (pinfunction "1_1") (pintype "passive"))
      (node (ref "R8") (pin "2") (pinfunction "2_2") (pintype "passive"))
      (node (ref "U$1") (pin "P60") (pinfunction "P6.1/A1_P60") (pintype "bidirectional"))
      (node (ref "Z2") (pin "1") (pinfunction "K_1") (pintype "bidirectional"))
    )
    (net (code "55") (name "Net-(U$1-P6.2{slash}A2)") (class "Default")
      (node (ref "R5") (pin "2") (pinfunction "2_2") (pintype "passive"))
      (node (ref "U$1") (pin "P61") (pinfunction "P6.2/A2_P61") (pintype "bidirectional"))
    )
    (net (code "56") (name "Net-(U$1-VREF+)") (class "Default")
      (node (ref "IC14") (pin "3") (pinfunction "3_3") (pintype "bidirectional"))
      (node (ref "U$1") (pin "P7") (pinfunction "VREF+_P7") (pintype "output"))
    )
    (net (code "57") (name "unconnected-(H1-Pad1)") (class "Default")
      (node (ref "H1") (pin "1") (pinfunction "1_1") (pintype "passive"))
    )
    (net (code "58") (name "unconnected-(H1AA-1-Pad33)") (class "Default")
      (node (ref "H1") (pin "33") (pinfunction "1_33") (pintype "passive"))
    )
    (net (code "59") (name "unconnected-(H1AB-1-Pad34)") (class "Default")
      (node (ref "H1") (pin "34") (pinfunction "1_34") (pintype "passive"))
    )
    (net (code "60") (name "unconnected-(H1AE-1-Pad37)") (class "Default")
      (node (ref "H1") (pin "37") (pinfunction "1_37") (pintype "passive"))
    )
    (net (code "61") (name "unconnected-(H1AF-1-Pad38)") (class "Default")
      (node (ref "H1") (pin "38") (pinfunction "1_38") (pintype "passive"))
    )
    (net (code "62") (name "unconnected-(H1AG-1-Pad39)") (class "Default")
      (node (ref "H1") (pin "39") (pinfunction "1_39") (pintype "passive"))
    )
    (net (code "63") (name "unconnected-(H1AH-1-Pad4)") (class "Default")
      (node (ref "H1") (pin "4") (pinfunction "1_4") (pintype "passive"))
    )
    (net (code "64") (name "unconnected-(H1AI-1-Pad40)") (class "Default")
      (node (ref "H1") (pin "40") (pinfunction "1_40") (pintype "passive"))
    )
    (net (code "65") (name "unconnected-(H1AK-1-Pad42)") (class "Default")
      (node (ref "H1") (pin "42") (pinfunction "1_42") (pintype "passive"))
    )
    (net (code "66") (name "unconnected-(H1AM-1-Pad44)") (class "Default")
      (node (ref "H1") (pin "44") (pinfunction "1_44") (pintype "passive"))
    )
    (net (code "67") (name "unconnected-(H1AN-1-Pad45)") (class "Default")
      (node (ref "H1") (pin "45") (pinfunction "1_45") (pintype "passive"))
    )
    (net (code "68") (name "unconnected-(H1AO-1-Pad46)") (class "Default")
      (node (ref "H1") (pin "46") (pinfunction "1_46") (pintype "passive"))
    )
    (net (code "69") (name "unconnected-(H1AP-1-Pad47)") (class "Default")
      (node (ref "H1") (pin "47") (pinfunction "1_47") (pintype "passive"))
    )
    (net (code "70") (name "unconnected-(H1AQ-1-Pad48)") (class "Default")
      (node (ref "H1") (pin "48") (pinfunction "1_48") (pintype "passive"))
    )
    (net (code "71") (name "unconnected-(H1AR-1-Pad49)") (class "Default")
      (node (ref "H1") (pin "49") (pinfunction "1_49") (pintype "passive"))
    )
    (net (code "72") (name "unconnected-(H1AS-1-Pad5)") (class "Default")
      (node (ref "H1") (pin "5") (pinfunction "1_5") (pintype "passive"))
    )
    (net (code "73") (name "unconnected-(H1AT-1-Pad50)") (class "Default")
      (node (ref "H1") (pin "50") (pinfunction "1_50") (pintype "passive"))
    )
    (net (code "74") (name "unconnected-(H1AU-1-Pad51)") (class "Default")
      (node (ref "H1") (pin "51") (pinfunction "1_51") (pintype "passive"))
    )
    (net (code "75") (name "unconnected-(H1AV-1-Pad52)") (class "Default")
      (node (ref "H1") (pin "52") (pinfunction "1_52") (pintype "passive"))
    )
    (net (code "76") (name "unconnected-(H1AW-1-Pad6)") (class "Default")
      (node (ref "H1") (pin "6") (pinfunction "1_6") (pintype "passive"))
    )
    (net (code "77") (name "unconnected-(H1AX-1-Pad7)") (class "Default")
      (node (ref "H1") (pin "7") (pinfunction "1_7") (pintype "passive"))
    )
    (net (code "78") (name "unconnected-(H1AY-1-Pad8)") (class "Default")
      (node (ref "H1") (pin "8") (pinfunction "1_8") (pintype "passive"))
    )
    (net (code "79") (name "unconnected-(H1AZ-1-Pad9)") (class "Default")
      (node (ref "H1") (pin "9") (pinfunction "1_9") (pintype "passive"))
    )
    (net (code "80") (name "unconnected-(H1B-1-Pad10)") (class "Default")
      (node (ref "H1") (pin "10") (pinfunction "1_10") (pintype "passive"))
    )
    (net (code "81") (name "unconnected-(H1C-1-Pad11)") (class "Default")
      (node (ref "H1") (pin "11") (pinfunction "1_11") (pintype "passive"))
    )
    (net (code "82") (name "unconnected-(H1D-1-Pad12)") (class "Default")
      (node (ref "H1") (pin "12") (pinfunction "1_12") (pintype "passive"))
    )
    (net (code "83") (name "unconnected-(H1E-1-Pad13)") (class "Default")
      (node (ref "H1") (pin "13") (pinfunction "1_13") (pintype "passive"))
    )
    (net (code "84") (name "unconnected-(H1F-1-Pad14)") (class "Default")
      (node (ref "H1") (pin "14") (pinfunction "1_14") (pintype "passive"))
    )
    (net (code "85") (name "unconnected-(H1G-1-Pad15)") (class "Default")
      (node (ref "H1") (pin "15") (pinfunction "1_15") (pintype "passive"))
    )
    (net (code "86") (name "unconnected-(H1H-1-Pad16)") (class "Default")
      (node (ref "H1") (pin "16") (pinfunction "1_16") (pintype "passive"))
    )
    (net (code "87") (name "unconnected-(H1I-1-Pad17)") (class "Default")
      (node (ref "H1") (pin "17") (pinfunction "1_17") (pintype "passive"))
    )
    (net (code "88") (name "unconnected-(H1J-1-Pad18)") (class "Default")
      (node (ref "H1") (pin "18") (pinfunction "1_18") (pintype "passive"))
    )
    (net (code "89") (name "unconnected-(H1L-1-Pad2)") (class "Default")
      (node (ref "H1") (pin "2") (pinfunction "1_2") (pintype "passive"))
    )
    (net (code "90") (name "unconnected-(H1S-1-Pad26)") (class "Default")
      (node (ref "H1") (pin "26") (pinfunction "1_26") (pintype "passive"))
    )
    (net (code "91") (name "unconnected-(H1T-1-Pad27)") (class "Default")
      (node (ref "H1") (pin "27") (pinfunction "1_27") (pintype "passive"))
    )
    (net (code "92") (name "unconnected-(H1U-1-Pad28)") (class "Default")
      (node (ref "H1") (pin "28") (pinfunction "1_28") (pintype "passive"))
    )
    (net (code "93") (name "unconnected-(H1W-1-Pad3)") (class "Default")
      (node (ref "H1") (pin "3") (pinfunction "1_3") (pintype "passive"))
    )
    (net (code "94") (name "unconnected-(H1X-1-Pad30)") (class "Default")
      (node (ref "H1") (pin "30") (pinfunction "1_30") (pintype "passive"))
    )
    (net (code "95") (name "unconnected-(H2-Pad1)") (class "Default")
      (node (ref "H2") (pin "1") (pinfunction "1_1") (pintype "passive"))
    )
    (net (code "96") (name "unconnected-(H2AA-1-Pad33)") (class "Default")
      (node (ref "H2") (pin "33") (pinfunction "1_33") (pintype "passive"))
    )
    (net (code "97") (name "unconnected-(H2AC-1-Pad35)") (class "Default")
      (node (ref "H2") (pin "35") (pinfunction "1_35") (pintype "passive"))
    )
    (net (code "98") (name "unconnected-(H2AD-1-Pad36)") (class "Default")
      (node (ref "H2") (pin "36") (pinfunction "1_36") (pintype "passive"))
    )
    (net (code "99") (name "unconnected-(H2AE-1-Pad37)") (class "Default")
      (node (ref "H2") (pin "37") (pinfunction "1_37") (pintype "passive"))
    )
    (net (code "100") (name "unconnected-(H2AF-1-Pad38)") (class "Default")
      (node (ref "H2") (pin "38") (pinfunction "1_38") (pintype "passive"))
    )
    (net (code "101") (name "unconnected-(H2AG-1-Pad39)") (class "Default")
      (node (ref "H2") (pin "39") (pinfunction "1_39") (pintype "passive"))
    )
    (net (code "102") (name "unconnected-(H2AH-1-Pad4)") (class "Default")
      (node (ref "H2") (pin "4") (pinfunction "1_4") (pintype "passive"))
    )
    (net (code "103") (name "unconnected-(H2AI-1-Pad40)") (class "Default")
      (node (ref "H2") (pin "40") (pinfunction "1_40") (pintype "passive"))
    )
    (net (code "104") (name "unconnected-(H2AJ-1-Pad41)") (class "Default")
      (node (ref "H2") (pin "41") (pinfunction "1_41") (pintype "passive"))
    )
    (net (code "105") (name "unconnected-(H2AK-1-Pad42)") (class "Default")
      (node (ref "H2") (pin "42") (pinfunction "1_42") (pintype "passive"))
    )
    (net (code "106") (name "unconnected-(H2AL-1-Pad43)") (class "Default")
      (node (ref "H2") (pin "43") (pinfunction "1_43") (pintype "passive"))
    )
    (net (code "107") (name "unconnected-(H2AM-1-Pad44)") (class "Default")
      (node (ref "H2") (pin "44") (pinfunction "1_44") (pintype "passive"))
    )
    (net (code "108") (name "unconnected-(H2AN-1-Pad45)") (class "Default")
      (node (ref "H2") (pin "45") (pinfunction "1_45") (pintype "passive"))
    )
    (net (code "109") (name "unconnected-(H2AO-1-Pad46)") (class "Default")
      (node (ref "H2") (pin "46") (pinfunction "1_46") (pintype "passive"))
    )
    (net (code "110") (name "unconnected-(H2AP-1-Pad47)") (class "Default")
      (node (ref "H2") (pin "47") (pinfunction "1_47") (pintype "passive"))
    )
    (net (code "111") (name "unconnected-(H2AQ-1-Pad48)") (class "Default")
      (node (ref "H2") (pin "48") (pinfunction "1_48") (pintype "passive"))
    )
    (net (code "112") (name "unconnected-(H2AR-1-Pad49)") (class "Default")
      (node (ref "H2") (pin "49") (pinfunction "1_49") (pintype "passive"))
    )
    (net (code "113") (name "unconnected-(H2AS-1-Pad5)") (class "Default")
      (node (ref "H2") (pin "5") (pinfunction "1_5") (pintype "passive"))
    )
    (net (code "114") (name "unconnected-(H2AT-1-Pad50)") (class "Default")
      (node (ref "H2") (pin "50") (pinfunction "1_50") (pintype "passive"))
    )
    (net (code "115") (name "unconnected-(H2AU-1-Pad51)") (class "Default")
      (node (ref "H2") (pin "51") (pinfunction "1_51") (pintype "passive"))
    )
    (net (code "116") (name "unconnected-(H2AV-1-Pad52)") (class "Default")
      (node (ref "H2") (pin "52") (pinfunction "1_52") (pintype "passive"))
    )
    (net (code "117") (name "unconnected-(H2AW-1-Pad6)") (class "Default")
      (node (ref "H2") (pin "6") (pinfunction "1_6") (pintype "passive"))
    )
    (net (code "118") (name "unconnected-(H2AX-1-Pad7)") (class "Default")
      (node (ref "H2") (pin "7") (pinfunction "1_7") (pintype "passive"))
    )
    (net (code "119") (name "unconnected-(H2AY-1-Pad8)") (class "Default")
      (node (ref "H2") (pin "8") (pinfunction "1_8") (pintype "passive"))
    )
    (net (code "120") (name "unconnected-(H2AZ-1-Pad9)") (class "Default")
      (node (ref "H2") (pin "9") (pinfunction "1_9") (pintype "passive"))
    )
    (net (code "121") (name "unconnected-(H2B-1-Pad10)") (class "Default")
      (node (ref "H2") (pin "10") (pinfunction "1_10") (pintype "passive"))
    )
    (net (code "122") (name "unconnected-(H2C-1-Pad11)") (class "Default")
      (node (ref "H2") (pin "11") (pinfunction "1_11") (pintype "passive"))
    )
    (net (code "123") (name "unconnected-(H2D-1-Pad12)") (class "Default")
      (node (ref "H2") (pin "12") (pinfunction "1_12") (pintype "passive"))
    )
    (net (code "124") (name "unconnected-(H2E-1-Pad13)") (class "Default")
      (node (ref "H2") (pin "13") (pinfunction "1_13") (pintype "passive"))
    )
    (net (code "125") (name "unconnected-(H2F-1-Pad14)") (class "Default")
      (node (ref "H2") (pin "14") (pinfunction "1_14") (pintype "passive"))
    )
    (net (code "126") (name "unconnected-(H2G-1-Pad15)") (class "Default")
      (node (ref "H2") (pin "15") (pinfunction "1_15") (pintype "passive"))
    )
    (net (code "127") (name "unconnected-(H2H-1-Pad16)") (class "Default")
      (node (ref "H2") (pin "16") (pinfunction "1_16") (pintype "passive"))
    )
    (net (code "128") (name "unconnected-(H2I-1-Pad17)") (class "Default")
      (node (ref "H2") (pin "17") (pinfunction "1_17") (pintype "passive"))
    )
    (net (code "129") (name "unconnected-(H2J-1-Pad18)") (class "Default")
      (node (ref "H2") (pin "18") (pinfunction "1_18") (pintype "passive"))
    )
    (net (code "130") (name "unconnected-(H2K-1-Pad19)") (class "Default")
      (node (ref "H2") (pin "19") (pinfunction "1_19") (pintype "passive"))
    )
    (net (code "131") (name "unconnected-(H2L-1-Pad2)") (class "Default")
      (node (ref "H2") (pin "2") (pinfunction "1_2") (pintype "passive"))
    )
    (net (code "132") (name "unconnected-(H2M-1-Pad20)") (class "Default")
      (node (ref "H2") (pin "20") (pinfunction "1_20") (pintype "passive"))
    )
    (net (code "133") (name "unconnected-(H2N-1-Pad21)") (class "Default")
      (node (ref "H2") (pin "21") (pinfunction "1_21") (pintype "passive"))
    )
    (net (code "134") (name "unconnected-(H2O-1-Pad22)") (class "Default")
      (node (ref "H2") (pin "22") (pinfunction "1_22") (pintype "passive"))
    )
    (net (code "135") (name "unconnected-(H2P-1-Pad23)") (class "Default")
      (node (ref "H2") (pin "23") (pinfunction "1_23") (pintype "passive"))
    )
    (net (code "136") (name "unconnected-(H2Q-1-Pad24)") (class "Default")
      (node (ref "H2") (pin "24") (pinfunction "1_24") (pintype "passive"))
    )
    (net (code "137") (name "unconnected-(H2R-1-Pad25)") (class "Default")
      (node (ref "H2") (pin "25") (pinfunction "1_25") (pintype "passive"))
    )
    (net (code "138") (name "unconnected-(H2S-1-Pad26)") (class "Default")
      (node (ref "H2") (pin "26") (pinfunction "1_26") (pintype "passive"))
    )
    (net (code "139") (name "unconnected-(H2T-1-Pad27)") (class "Default")
      (node (ref "H2") (pin "27") (pinfunction "1_27") (pintype "passive"))
    )
    (net (code "140") (name "unconnected-(H2U-1-Pad28)") (class "Default")
      (node (ref "H2") (pin "28") (pinfunction "1_28") (pintype "passive"))
    )
    (net (code "141") (name "unconnected-(H2W-1-Pad3)") (class "Default")
      (node (ref "H2") (pin "3") (pinfunction "1_3") (pintype "passive"))
    )
    (net (code "142") (name "unconnected-(H2Y-1-Pad31)") (class "Default")
      (node (ref "H2") (pin "31") (pinfunction "1_31") (pintype "passive"))
    )
    (net (code "143") (name "unconnected-(IC1-A1-Pad6)") (class "Default")
      (node (ref "IC1") (pin "6") (pinfunction "A1_6") (pintype "bidirectional"))
    )
    (net (code "144") (name "unconnected-(IC1-A2-Pad11)") (class "Default")
      (node (ref "IC1") (pin "11") (pinfunction "A2_11") (pintype "bidirectional"))
    )
    (net (code "145") (name "unconnected-(IC2-OUT_(TAB)-Pad4)") (class "Default")
      (node (ref "IC2") (pin "4") (pinfunction "OUT_(TAB)_4") (pintype "output"))
    )
    (net (code "146") (name "unconnected-(IC3-Pad3)") (class "Default")
      (node (ref "IC3") (pin "3") (pinfunction "3_3") (pintype "bidirectional"))
    )
    (net (code "147") (name "unconnected-(IC4-Pad3)") (class "Default")
      (node (ref "IC4") (pin "3") (pinfunction "3_3") (pintype "bidirectional"))
    )
    (net (code "148") (name "unconnected-(IC5-Pad3)") (class "Default")
      (node (ref "IC5") (pin "3") (pinfunction "3_3") (pintype "bidirectional"))
    )
    (net (code "149") (name "unconnected-(IC6-Pad3)") (class "Default")
      (node (ref "IC6") (pin "3") (pinfunction "3_3") (pintype "bidirectional"))
    )
    (net (code "150") (name "unconnected-(IC7-Pad3)") (class "Default")
      (node (ref "IC7") (pin "3") (pinfunction "3_3") (pintype "bidirectional"))
    )
    (net (code "151") (name "unconnected-(IC8-Pad3)") (class "Default")
      (node (ref "IC8") (pin "3") (pinfunction "3_3") (pintype "bidirectional"))
    )
    (net (code "152") (name "unconnected-(IC9-Pad3)") (class "Default")
      (node (ref "IC9") (pin "3") (pinfunction "3_3") (pintype "bidirectional"))
    )
    (net (code "153") (name "unconnected-(IC10-Pad3)") (class "Default")
      (node (ref "IC10") (pin "3") (pinfunction "3_3") (pintype "bidirectional"))
    )
    (net (code "154") (name "unconnected-(IC11-Pad3)") (class "Default")
      (node (ref "IC11") (pin "3") (pinfunction "3_3") (pintype "bidirectional"))
    )
    (net (code "155") (name "unconnected-(IC12-Pad3)") (class "Default")
      (node (ref "IC12") (pin "3") (pinfunction "3_3") (pintype "bidirectional"))
    )
    (net (code "156") (name "unconnected-(IC13-Pad3)") (class "Default")
      (node (ref "IC13") (pin "3") (pinfunction "3_3") (pintype "bidirectional"))
    )
    (net (code "157") (name "unconnected-(IC15-OUT_(TAB)-Pad4)") (class "Default")
      (node (ref "IC15") (pin "4") (pinfunction "OUT_(TAB)_4") (pintype "output"))
    )
    (net (code "158") (name "unconnected-(IC16-A1-Pad6)") (class "Default")
      (node (ref "IC16") (pin "6") (pinfunction "A1_6") (pintype "bidirectional"))
    )
    (net (code "159") (name "unconnected-(IC16-A2-Pad11)") (class "Default")
      (node (ref "IC16") (pin "11") (pinfunction "A2_11") (pintype "bidirectional"))
    )
    (net (code "160") (name "unconnected-(IC17-Pad3)") (class "Default")
      (node (ref "IC17") (pin "3") (pinfunction "3_3") (pintype "bidirectional"))
    )
    (net (code "161") (name "unconnected-(IC18-Pad3)") (class "Default")
      (node (ref "IC18") (pin "3") (pinfunction "3_3") (pintype "bidirectional"))
    )
    (net (code "162") (name "unconnected-(IC19-Pad3)") (class "Default")
      (node (ref "IC19") (pin "3") (pinfunction "3_3") (pintype "bidirectional"))
    )
    (net (code "163") (name "unconnected-(IC20-Pad3)") (class "Default")
      (node (ref "IC20") (pin "3") (pinfunction "3_3") (pintype "bidirectional"))
    )
    (net (code "164") (name "unconnected-(IC21-Pad3)") (class "Default")
      (node (ref "IC21") (pin "3") (pinfunction "3_3") (pintype "bidirectional"))
    )
    (net (code "165") (name "unconnected-(IC22-Pad3)") (class "Default")
      (node (ref "IC22") (pin "3") (pinfunction "3_3") (pintype "bidirectional"))
    )
    (net (code "166") (name "unconnected-(IC23-Pad3)") (class "Default")
      (node (ref "IC23") (pin "3") (pinfunction "3_3") (pintype "bidirectional"))
    )
    (net (code "167") (name "unconnected-(IC24-Pad3)") (class "Default")
      (node (ref "IC24") (pin "3") (pinfunction "3_3") (pintype "bidirectional"))
    )
    (net (code "168") (name "unconnected-(IC25-OUT_(TAB)-Pad4)") (class "Default")
      (node (ref "IC25") (pin "4") (pinfunction "OUT_(TAB)_4") (pintype "output"))
    )
    (net (code "169") (name "unconnected-(J1-DAT1-Pad8)") (class "Default")
      (node (ref "J1") (pin "8") (pinfunction "DAT1_8") (pintype "bidirectional"))
    )
    (net (code "170") (name "unconnected-(J1-DAT2-Pad1)") (class "Default")
      (node (ref "J1") (pin "1") (pinfunction "DAT2_1") (pintype "bidirectional"))
    )
    (net (code "171") (name "unconnected-(U$1-P4.1{slash}TB1-PadP37)") (class "Default")
      (node (ref "U$1") (pin "P37") (pinfunction "P4.1/TB1_P37") (pintype "bidirectional"))
    )
    (net (code "172") (name "unconnected-(U$1-P4.2{slash}TB2-PadP38)") (class "Default")
      (node (ref "U$1") (pin "P38") (pinfunction "P4.2/TB2_P38") (pintype "bidirectional"))
    )
    (net (code "173") (name "unconnected-(U$1-P4.3{slash}TB3-PadP39)") (class "Default")
      (node (ref "U$1") (pin "P39") (pinfunction "P4.3/TB3_P39") (pintype "bidirectional"))
    )
    (net (code "174") (name "unconnected-(U$1-P4.4{slash}TB4-PadP40)") (class "Default")
      (node (ref "U$1") (pin "P40") (pinfunction "P4.4/TB4_P40") (pintype "bidirectional"))
    )
    (net (code "175") (name "unconnected-(U$1-P4.5{slash}TB5-PadP41)") (class "Default")
      (node (ref "U$1") (pin "P41") (pinfunction "P4.5/TB5_P41") (pintype "bidirectional"))
    )
    (net (code "176") (name "unconnected-(U$1-P4.6{slash}TB6-PadP42)") (class "Default")
      (node (ref "U$1") (pin "P42") (pinfunction "P4.6/TB6_P42") (pintype "bidirectional"))
    )
    (net (code "177") (name "unconnected-(U$1-P4.7{slash}TBCLK-PadP43)") (class "Default")
      (node (ref "U$1") (pin "P43") (pinfunction "P4.7/TBCLK_P43") (pintype "bidirectional"))
    )
    (net (code "178") (name "unconnected-(U$1-P5.3{slash}UCB1CLK{slash}UCA1STE-PadP47)") (class "Default")
      (node (ref "U$1") (pin "P47") (pinfunction "P5.3/UCB1CLK/UCA1STE_P47") (pintype "bidirectional"))
    )
    (net (code "179") (name "unconnected-(U$1-P5.4{slash}MCLK-PadP48)") (class "Default")
      (node (ref "U$1") (pin "P48") (pinfunction "P5.4/MCLK_P48") (pintype "bidirectional"))
    )
    (net (code "180") (name "unconnected-(U$1-P5.5{slash}SMCLK-PadP49)") (class "Default")
      (node (ref "U$1") (pin "P49") (pinfunction "P5.5/SMCLK_P49") (pintype "bidirectional"))
    )
    (net (code "181") (name "unconnected-(U$1-P5.6{slash}ACLK-PadP50)") (class "Default")
      (node (ref "U$1") (pin "P50") (pinfunction "P5.6/ACLK_P50") (pintype "bidirectional"))
    )
    (net (code "182") (name "unconnected-(U$1-P5.7{slash}TBOUTH{slash}SVSOUT-PadP51)") (class "Default")
      (node (ref "U$1") (pin "P51") (pinfunction "P5.7/TBOUTH/SVSOUT_P51") (pintype "bidirectional"))
    )
    (net (code "183") (name "unconnected-(U$1-P6.3{slash}A3-PadP2)") (class "Default")
      (node (ref "U$1") (pin "P2") (pinfunction "P6.3/A3_P2") (pintype "bidirectional"))
    )
    (net (code "184") (name "unconnected-(U$1-P6.4{slash}A4-PadP3)") (class "Default")
      (node (ref "U$1") (pin "P3") (pinfunction "P6.4/A4_P3") (pintype "bidirectional"))
    )
    (net (code "185") (name "unconnected-(U$1-P6.5{slash}A5-PadP4)") (class "Default")
      (node (ref "U$1") (pin "P4") (pinfunction "P6.5/A5_P4") (pintype "bidirectional"))
    )
    (net (code "186") (name "unconnected-(U$1-P6.6{slash}A6-PadP5)") (class "Default")
      (node (ref "U$1") (pin "P5") (pinfunction "P6.6/A6_P5") (pintype "bidirectional"))
    )
    (net (code "187") (name "unconnected-(U$1-P6.7{slash}A7{slash}SVSIN-PadP6)") (class "Default")
      (node (ref "U$1") (pin "P6") (pinfunction "P6.7/A7/SVSIN_P6") (pintype "bidirectional"))
    )
    (net (code "188") (name "unconnected-(U$1-TCK-PadP57)") (class "Default")
      (node (ref "U$1") (pin "P57") (pinfunction "TCK_P57") (pintype "input"))
    )
    (net (code "189") (name "unconnected-(U$1-TDI{slash}TCLK-PadP55)") (class "Default")
      (node (ref "U$1") (pin "P55") (pinfunction "TDI/TCLK_P55") (pintype "input"))
    )
    (net (code "190") (name "unconnected-(U$1-TDO{slash}TDI-PadP54)") (class "Default")
      (node (ref "U$1") (pin "P54") (pinfunction "TDO/TDI_P54") (pintype "bidirectional"))
    )
    (net (code "191") (name "unconnected-(U$1-TMS-PadP56)") (class "Default")
      (node (ref "U$1") (pin "P56") (pinfunction "TMS_P56") (pintype "input"))
    )
    (net (code "192") (name "unconnected-(U$1-VEREF+-PadP10)") (class "Default")
      (node (ref "U$1") (pin "P10") (pinfunction "VEREF+_P10") (pintype "input"))
    )
    (net (code "193") (name "unconnected-(U$1-VREF-{slash}VEREF-PadP11)") (class "Default")
      (node (ref "U$1") (pin "P11") (pinfunction "VREF-/VEREF_P11") (pintype "input"))
    )
    (net (code "194") (name "unconnected-(U$1-XIN-PadP8)") (class "Default")
      (node (ref "U$1") (pin "P8") (pinfunction "XIN_P8") (pintype "input"))
    )
    (net (code "195") (name "unconnected-(U$1-XOUT-PadP9)") (class "Default")
      (node (ref "U$1") (pin "P9") (pinfunction "XOUT_P9") (pintype "output"))
    )
    (net (code "196") (name "unconnected-(U$1-XT2IN-PadP53)") (class "Default")
      (node (ref "U$1") (pin "P53") (pinfunction "XT2IN_P53") (pintype "input"))
    )
    (net (code "197") (name "unconnected-(U$1-XT2OUT-PadP52)") (class "Default")
      (node (ref "U$1") (pin "P52") (pinfunction "XT2OUT_P52") (pintype "output"))
    )
    (net (code "198") (name "unconnected-(U$1-~{RST{slash}NMI}-PadP58)") (class "Default")
      (node (ref "U$1") (pin "P58") (pinfunction "~{RST/NMI}_P58") (pintype "input"))
    )
  )
)
